# MeasureComponents.net
KiCad netlist of a schematic drawn in EAGLE
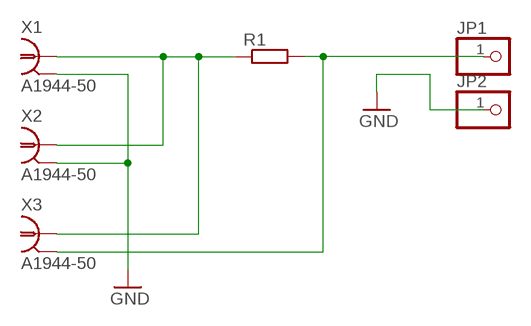
[diagram p0: schematic, sheet 1]

(export (version "E")
  (design (tool "Eeschema 10.0.6"))
  (components
    (comp (ref "JP1")
      (value "PINHD-1X1")
      (footprint "eagle-import:1X01")
      (libsource (lib "eagle-import") (part "PINHD-1X1"))
    )
    (comp (ref "JP2")
      (value "PINHD-1X1")
      (footprint "eagle-import:1X01")
      (libsource (lib "eagle-import") (part "PINHD-1X1"))
    )
    (comp (ref "R1")
      (value "R-EU_M1206")
      (footprint "eagle-import:M1206")
      (libsource (lib "eagle-import") (part "R-EU_M1206"))
    )
    (comp (ref "X1")
      (value "A1944-50")
      (footprint "eagle-import:A1944")
      (libsource (lib "eagle-import") (part "A1944-50"))
    )
    (comp (ref "X2")
      (value "A1944-50")
      (footprint "eagle-import:A1944")
      (libsource (lib "eagle-import") (part "A1944-50"))
    )
    (comp (ref "X3")
      (value "A1944-50")
      (footprint "eagle-import:A1944")
      (libsource (lib "eagle-import") (part "A1944-50"))
    )
  )
  (nets
    (net (code "1") (name "GND") (class "Default")
      (node (ref "JP2") (pin "1") (pinfunction "1_1") (pintype "passive"))
      (node (ref "X1") (pin "2") (pinfunction "2_2") (pintype "passive"))
      (node (ref "X1") (pin "3") (pinfunction "2_3") (pintype "passive"))
      (node (ref "X1") (pin "4") (pinfunction "2_4") (pintype "passive"))
      (node (ref "X1") (pin "5") (pinfunction "2_5") (pintype "passive"))
      (node (ref "X2") (pin "2") (pinfunction "2_2") (pintype "passive"))
      (node (ref "X2") (pin "3") (pinfunction "2_3") (pintype "passive"))
      (node (ref "X2") (pin "4") (pinfunction "2_4") (pintype "passive"))
      (node (ref "X2") (pin "5") (pinfunction "2_5") (pintype "passive"))
    )
    (net (code "2") (name "Net-(JP1-Pad1)") (class "Default")
      (node (ref "JP1") (pin "1") (pinfunction "1_1") (pintype "passive"))
      (node (ref "R1") (pin "2") (pinfunction "2_2") (pintype "passive"))
      (node (ref "X3") (pin "2") (pinfunction "2_2") (pintype "passive"))
      (node (ref "X3") (pin "3") (pinfunction "2_3") (pintype "passive"))
      (node (ref "X3") (pin "4") (pinfunction "2_4") (pintype "passive"))
      (node (ref "X3") (pin "5") (pinfunction "2_5") (pintype "passive"))
    )
    (net (code "3") (name "Net-(R1-Pad1)") (class "Default")
      (node (ref "R1") (pin "1") (pinfunction "1_1") (pintype "passive"))
      (node (ref "X1") (pin "1") (pinfunction "1_1") (pintype "passive"))
      (node (ref "X2") (pin "1") (pinfunction "1_1") (pintype "passive"))
      (node (ref "X3") (pin "1") (pinfunction "1_1") (pintype "passive"))
    )
  )
)
